# proiect2025_v18.net
KiCad netlist of a schematic drawn in EAGLE
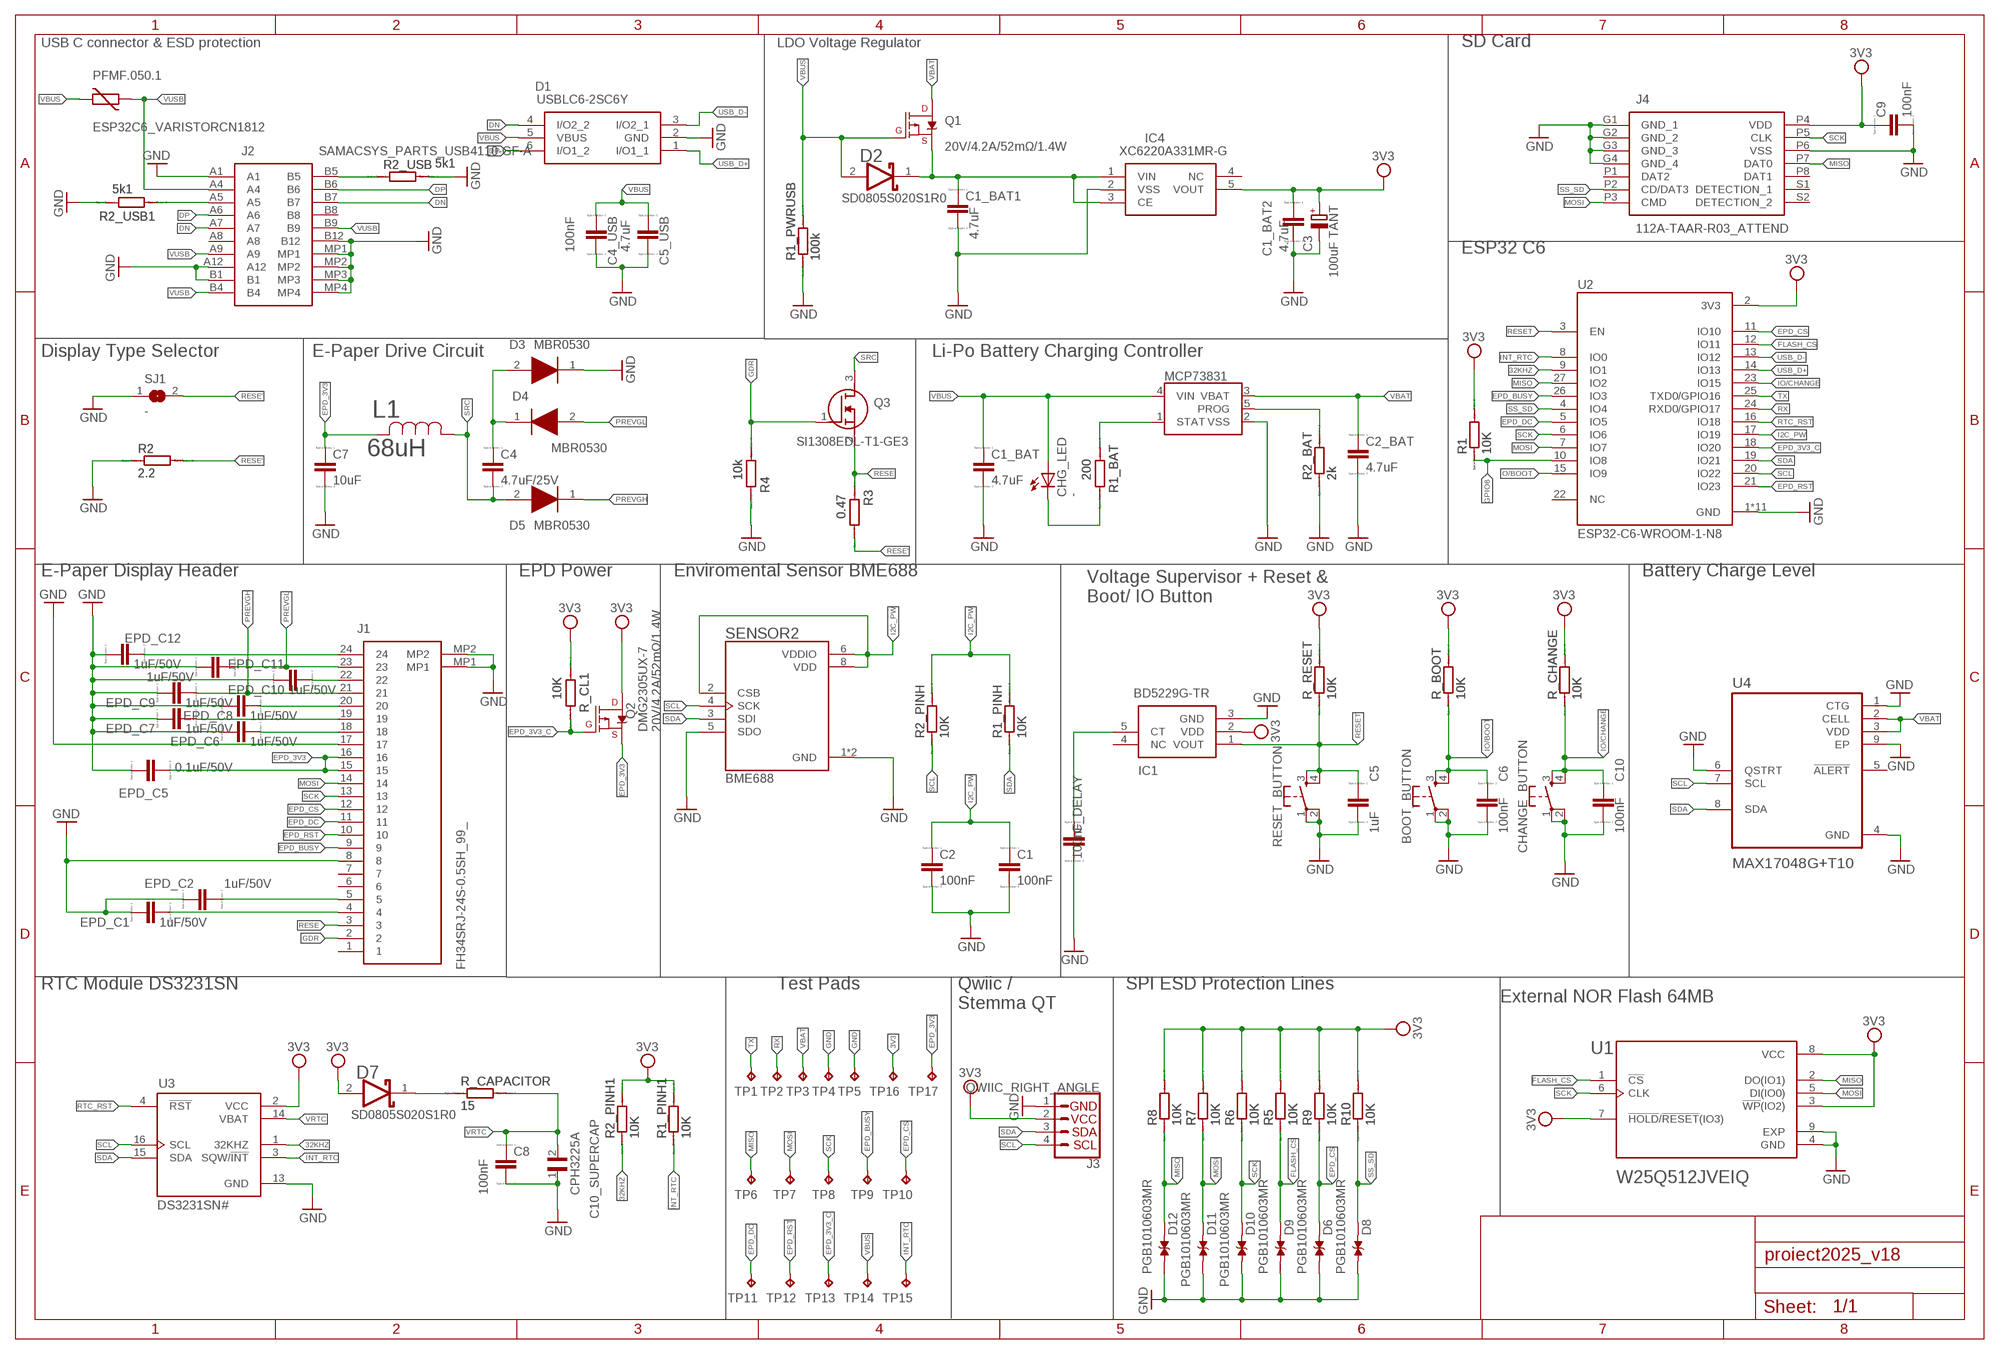
[diagram p0: schematic, sheet 1]

(export (version "E")
  (design (tool "Eeschema 10.0.6"))
  (components
    (comp (ref "BOOT_BUTTON")
      (value "BUTTON_CUSYOMV1")
      (footprint "eagle-import:MYBUTTON")
      (libsource (lib "eagle-import") (part "BUTTON_CUSYOMV1"))
    )
    (comp (ref "C1")
      (value "100nF")
      (footprint "eagle-import:EAGLE-LTSPICE_C0402")
      (libsource (lib "eagle-import") (part "EAGLE-LTSPICE_CC0402"))
    )
    (comp (ref "C1_BAT")
      (value "4.7uF")
      (footprint "eagle-import:EAGLE-LTSPICE_C0402")
      (libsource (lib "eagle-import") (part "EAGLE-LTSPICE_CC0402"))
    )
    (comp (ref "C1_BAT1")
      (value "4.7uF")
      (footprint "eagle-import:EAGLE-LTSPICE_C0402")
      (libsource (lib "eagle-import") (part "EAGLE-LTSPICE_CC0402"))
    )
    (comp (ref "C1_BAT2")
      (value "4.7uF")
      (footprint "eagle-import:EAGLE-LTSPICE_C0402")
      (libsource (lib "eagle-import") (part "EAGLE-LTSPICE_CC0402"))
    )
    (comp (ref "C2")
      (value "100nF")
      (footprint "eagle-import:EAGLE-LTSPICE_C0402")
      (libsource (lib "eagle-import") (part "EAGLE-LTSPICE_CC0402"))
    )
    (comp (ref "C2_BAT")
      (value "4.7uF")
      (footprint "eagle-import:EAGLE-LTSPICE_C0402")
      (libsource (lib "eagle-import") (part "EAGLE-LTSPICE_CC0402"))
    )
    (comp (ref "C3")
      (value "100uF TANT")
      (footprint "eagle-import:RCL_CT3528")
      (libsource (lib "eagle-import") (part "RCL_CPOL-EUCT3528"))
    )
    (comp (ref "C4")
      (value "4.7uF/25V")
      (footprint "eagle-import:EAGLE-LTSPICE_C0402")
      (libsource (lib "eagle-import") (part "EAGLE-LTSPICE_CC0402"))
    )
    (comp (ref "C4_USB")
      (value "100nF")
      (footprint "eagle-import:EAGLE-LTSPICE_C0402")
      (libsource (lib "eagle-import") (part "EAGLE-LTSPICE_CC0402"))
    )
    (comp (ref "C5")
      (value "1uF")
      (footprint "eagle-import:EAGLE-LTSPICE_C0402")
      (libsource (lib "eagle-import") (part "EAGLE-LTSPICE_CC0402"))
    )
    (comp (ref "C5_USB")
      (value "4.7uF")
      (footprint "eagle-import:EAGLE-LTSPICE_C0402")
      (libsource (lib "eagle-import") (part "EAGLE-LTSPICE_CC0402"))
    )
    (comp (ref "C6")
      (value "100nF")
      (footprint "eagle-import:EAGLE-LTSPICE_C0402")
      (libsource (lib "eagle-import") (part "EAGLE-LTSPICE_CC0402"))
    )
    (comp (ref "C7")
      (value "10uF")
      (footprint "eagle-import:EAGLE-LTSPICE_C0402")
      (libsource (lib "eagle-import") (part "EAGLE-LTSPICE_CC0402"))
    )
    (comp (ref "C8")
      (value "100nF")
      (footprint "eagle-import:EAGLE-LTSPICE_C0402")
      (libsource (lib "eagle-import") (part "EAGLE-LTSPICE_CC0402"))
    )
    (comp (ref "C9")
      (value "100nF")
      (footprint "eagle-import:EAGLE-LTSPICE_C0402")
      (libsource (lib "eagle-import") (part "EAGLE-LTSPICE_CC0402"))
    )
    (comp (ref "C10")
      (value "100nF")
      (footprint "eagle-import:EAGLE-LTSPICE_C0402")
      (libsource (lib "eagle-import") (part "EAGLE-LTSPICE_CC0402"))
    )
    (comp (ref "C10_SUPERCAP")
      (value "CPH3225A")
      (footprint "eagle-import:CAPCP3225X100N")
      (fields (field (name "MF") "Seiko Instruments"))
      (libsource (lib "eagle-import") (part "CPH3225A"))
    )
    (comp (ref "CHANGE_BUTTON")
      (value "BUTTON_CUSYOMV1")
      (footprint "eagle-import:MYBUTTON")
      (libsource (lib "eagle-import") (part "BUTTON_CUSYOMV1"))
    )
    (comp (ref "CHG_LED")
      (value "-")
      (footprint "eagle-import:ADAFRUIT_CHIP-LED0603")
      (libsource (lib "eagle-import") (part "ADAFRUIT_LEDCHIP-LED0603"))
    )
    (comp (ref "C_DELAY")
      (value "100nF")
      (footprint "eagle-import:EAGLE-LTSPICE_C0402")
      (libsource (lib "eagle-import") (part "EAGLE-LTSPICE_CC0402"))
    )
    (comp (ref "D1")
      (value "USBLC6-2SC6Y")
      (footprint "eagle-import:SOT95P280X145-6N")
      (fields (field (name "MF") "STMicroelectronics"))
      (libsource (lib "eagle-import") (part "USBLC6-2SC6Y"))
    )
    (comp (ref "D2")
      (value "ESP32_WROVER_AVX---SD0805S020S1R0_AVX_SD0805S020S1R0_0_0AVX_SD0805S020S1R0_0_0")
      (footprint "eagle-import:ESP32_WROVER_AVX---SD0805S020S1R0_AVX_SD0805S020S1R0_0")
      (fields
        (field (name "DIGIKEY_PART_NUMBER") "478-7800-1-ND")
        (field (name "MF") "AVX")
        (field (name "MOUSER_PART_NUMBER") "581-SD0805S020S1R0")
      )
      (libsource (lib "eagle-import") (part "ESP32_WROVER_AVX---SD0805S020S1R0_AVX_SD0805S020S1R0_0_0AVX_SD0805S020S1R0_0_0"))
    )
    (comp (ref "D3")
      (value "MBR0530")
      (footprint "eagle-import:SOD3716X135N")
      (fields (field (name "MF") "ON Semiconductor"))
      (libsource (lib "eagle-import") (part "MBR0530"))
    )
    (comp (ref "D4")
      (value "MBR0530")
      (footprint "eagle-import:SOD3716X135N")
      (fields (field (name "MF") "ON Semiconductor"))
      (libsource (lib "eagle-import") (part "MBR0530"))
    )
    (comp (ref "D5")
      (value "MBR0530")
      (footprint "eagle-import:SOD3716X135N")
      (fields (field (name "MF") "ON Semiconductor"))
      (libsource (lib "eagle-import") (part "MBR0530"))
    )
    (comp (ref "D6")
      (value "PGB1010603MR")
      (footprint "eagle-import:DIOC1608X36N")
      (fields (field (name "MF") "Littelfuse Inc."))
      (libsource (lib "eagle-import") (part "PGB1010603MR"))
    )
    (comp (ref "D7")
      (value "ESP32_WROVER_AVX---SD0805S020S1R0_AVX_SD0805S020S1R0_0_0AVX_SD0805S020S1R0_0_0")
      (footprint "eagle-import:ESP32_WROVER_AVX---SD0805S020S1R0_AVX_SD0805S020S1R0_0")
      (fields
        (field (name "DIGIKEY_PART_NUMBER") "478-7800-1-ND")
        (field (name "MF") "AVX")
        (field (name "MOUSER_PART_NUMBER") "581-SD0805S020S1R0")
      )
      (libsource (lib "eagle-import") (part "ESP32_WROVER_AVX---SD0805S020S1R0_AVX_SD0805S020S1R0_0_0AVX_SD0805S020S1R0_0_0"))
    )
    (comp (ref "D8")
      (value "PGB1010603MR")
      (footprint "eagle-import:DIOC1608X36N")
      (fields (field (name "MF") "Littelfuse Inc."))
      (libsource (lib "eagle-import") (part "PGB1010603MR"))
    )
    (comp (ref "D9")
      (value "PGB1010603MR")
      (footprint "eagle-import:DIOC1608X36N")
      (fields (field (name "MF") "Littelfuse Inc."))
      (libsource (lib "eagle-import") (part "PGB1010603MR"))
    )
    (comp (ref "D10")
      (value "PGB1010603MR")
      (footprint "eagle-import:DIOC1608X36N")
      (fields (field (name "MF") "Littelfuse Inc."))
      (libsource (lib "eagle-import") (part "PGB1010603MR"))
    )
    (comp (ref "D11")
      (value "PGB1010603MR")
      (footprint "eagle-import:DIOC1608X36N")
      (fields (field (name "MF") "Littelfuse Inc."))
      (libsource (lib "eagle-import") (part "PGB1010603MR"))
    )
    (comp (ref "D12")
      (value "PGB1010603MR")
      (footprint "eagle-import:DIOC1608X36N")
      (fields (field (name "MF") "Littelfuse Inc."))
      (libsource (lib "eagle-import") (part "PGB1010603MR"))
    )
    (comp (ref "EPD_C1")
      (value "1uF/50V")
      (footprint "eagle-import:EAGLE-LTSPICE_C0402")
      (libsource (lib "eagle-import") (part "EAGLE-LTSPICE_CC0402"))
    )
    (comp (ref "EPD_C2")
      (value "1uF/50V")
      (footprint "eagle-import:EAGLE-LTSPICE_C0402")
      (libsource (lib "eagle-import") (part "EAGLE-LTSPICE_CC0402"))
    )
    (comp (ref "EPD_C5")
      (value "0.1uF/50V")
      (footprint "eagle-import:EAGLE-LTSPICE_C0402")
      (libsource (lib "eagle-import") (part "EAGLE-LTSPICE_CC0402"))
    )
    (comp (ref "EPD_C6")
      (value "1uF/50V")
      (footprint "eagle-import:EAGLE-LTSPICE_C0402")
      (libsource (lib "eagle-import") (part "EAGLE-LTSPICE_CC0402"))
    )
    (comp (ref "EPD_C7")
      (value "1uF/50V")
      (footprint "eagle-import:EAGLE-LTSPICE_C0402")
      (libsource (lib "eagle-import") (part "EAGLE-LTSPICE_CC0402"))
    )
    (comp (ref "EPD_C8")
      (value "1uF/50V")
      (footprint "eagle-import:EAGLE-LTSPICE_C0402")
      (libsource (lib "eagle-import") (part "EAGLE-LTSPICE_CC0402"))
    )
    (comp (ref "EPD_C9")
      (value "1uF/50V")
      (footprint "eagle-import:EAGLE-LTSPICE_C0402")
      (libsource (lib "eagle-import") (part "EAGLE-LTSPICE_CC0402"))
    )
    (comp (ref "EPD_C10")
      (value "1uF/50V")
      (footprint "eagle-import:EAGLE-LTSPICE_C0402")
      (libsource (lib "eagle-import") (part "EAGLE-LTSPICE_CC0402"))
    )
    (comp (ref "EPD_C11")
      (value "1uF/50V")
      (footprint "eagle-import:EAGLE-LTSPICE_C0402")
      (libsource (lib "eagle-import") (part "EAGLE-LTSPICE_CC0402"))
    )
    (comp (ref "EPD_C12")
      (value "1uF/50V")
      (footprint "eagle-import:EAGLE-LTSPICE_C0402")
      (libsource (lib "eagle-import") (part "EAGLE-LTSPICE_CC0402"))
    )
    (comp (ref "IC1")
      (value "BD5229G-TR")
      (footprint "eagle-import:SOT95P280X125-5N")
      (fields (field (name "MOUSER_PART_NUMBER") "755-BD5229G-TR"))
      (libsource (lib "eagle-import") (part "BD5229G-TR"))
    )
    (comp (ref "IC4")
      (value "XC6220A331MR-G")
      (footprint "eagle-import:SOT95P280X120-5N")
      (fields (field (name "MOUSER_PART_NUMBER") "865-XC6220A331MR-G"))
      (libsource (lib "eagle-import") (part "XC6220A331MR-G"))
    )
    (comp (ref "J1")
      (value "FH34SRJ-24S-0.5SH_99_")
      (footprint "eagle-import:FH34SRJ24S05SH99")
      (fields
        (field (name "MANUFACTURER_PART_NUMBER") "FH34SRJ-24S-0.5SH(99)")
        (field (name "MOUSER_PART_NUMBER") "798-FH34SRJ24S05SH99")
      )
      (libsource (lib "eagle-import") (part "FH34SRJ-24S-0.5SH_99_"))
    )
    (comp (ref "J2")
      (value "SAMACSYS_PARTS_USB4110-GF-A")
      (footprint "eagle-import:SAMACSYS_PARTS_USB4110GFA")
      (fields
        (field (name "MANUFACTURER_PART_NUMBER") "USB4110-GF-A")
        (field (name "MOUSER_PART_NUMBER") "640-USB4110-GF-A")
      )
      (libsource (lib "eagle-import") (part "SAMACSYS_PARTS_USB4110-GF-A"))
    )
    (comp (ref "J3")
      (value "QWIIC_RIGHT_ANGLE")
      (footprint "eagle-import:JST04_1MM_RA")
      (libsource (lib "eagle-import") (part "QWIIC_CONNECTORJS-1MM"))
    )
    (comp (ref "J4")
      (value "112A-TAAR-R03_ATTEND")
      (footprint "eagle-import:112ATAARR03ATTEND")
      (fields (field (name "MANUFACTURER_PART_NUMBER") "112A-TAAR-R03 ATTEND"))
      (libsource (lib "eagle-import") (part "112A-TAAR-R03_ATTEND"))
    )
    (comp (ref "L1")
      (value "68uH")
      (footprint "eagle-import:IND_4828-WE-TPC_WRE")
      (fields
        (field (name "MANUFACTURER_PART_NUMBER") "744043680")
        (field (name "COPYRIGHT") "Copyright (C) 2024 Ultra Librarian. All rights reserved.")
      )
      (libsource (lib "eagle-import") (part "744043680IND_4828-WE-TPC_WRE"))
    )
    (comp (ref "MCP73831")
      (value "ESP32_WROVER_SPARKFUN-IC-POWER_MCP73831")
      (footprint "eagle-import:ESP32_WROVER_SPARKFUN-IC-POWER_SOT23-5")
      (libsource (lib "eagle-import") (part "ESP32_WROVER_SPARKFUN-IC-POWER_MCP73831"))
    )
    (comp (ref "PFMF.050.1")
      (value "ESP32C6_VARISTORCN1812")
      (footprint "eagle-import:ESP32C6_VARISTOR_CT_CN1812")
      (libsource (lib "eagle-import") (part "ESP32C6_VARISTORCN1812"))
    )
    (comp (ref "Q1")
      (value "20V/4.2A/52mΩ/1.4W")
      (footprint "eagle-import:ESP32_WROVER_SPARKFUN-DISCRETESEMI_SOT23-3")
      (libsource (lib "eagle-import") (part "ESP32_WROVER_SPARKFUN-DISCRETESEMI_MOSFET_PCH-DMG2305UX-7"))
    )
    (comp (ref "Q2")
      (value "20V/4.2A/52mΩ/1.4W")
      (footprint "eagle-import:ESP32_WROVER_SPARKFUN-DISCRETESEMI_SOT23-3")
      (libsource (lib "eagle-import") (part "ESP32_WROVER_SPARKFUN-DISCRETESEMI_MOSFET_PCH-DMG2305UX-7"))
    )
    (comp (ref "Q3")
      (value "SI1308EDL-T1-GE3")
      (footprint "eagle-import:SOT65P210X110-3N")
      (fields (field (name "MF") "Vishay Siliconix"))
      (libsource (lib "eagle-import") (part "SI1308EDL-T1-GE3"))
    )
    (comp (ref "R1")
      (value "10K")
      (footprint "eagle-import:ESP32_WROVER_EAGLE-LTSPICE_R0402")
      (libsource (lib "eagle-import") (part "ESP32_WROVER_EAGLE-LTSPICE_RR0402"))
    )
    (comp (ref "R1_BAT")
      (value "200")
      (footprint "eagle-import:ESP32_WROVER_EAGLE-LTSPICE_R0402")
      (libsource (lib "eagle-import") (part "ESP32_WROVER_EAGLE-LTSPICE_RR0402"))
    )
    (comp (ref "R1_PINH")
      (value "10K")
      (footprint "eagle-import:ESP32_WROVER_EAGLE-LTSPICE_R0402")
      (libsource (lib "eagle-import") (part "ESP32_WROVER_EAGLE-LTSPICE_RR0402"))
    )
    (comp (ref "R1_PINH1")
      (value "10K")
      (footprint "eagle-import:ESP32_WROVER_EAGLE-LTSPICE_R0402")
      (libsource (lib "eagle-import") (part "ESP32_WROVER_EAGLE-LTSPICE_RR0402"))
    )
    (comp (ref "R1_PWRUSB")
      (value "100k")
      (footprint "eagle-import:ESP32_WROVER_EAGLE-LTSPICE_R0402")
      (libsource (lib "eagle-import") (part "ESP32_WROVER_EAGLE-LTSPICE_RR0402"))
    )
    (comp (ref "R2")
      (value "2.2")
      (footprint "eagle-import:ESP32_WROVER_EAGLE-LTSPICE_R0402")
      (libsource (lib "eagle-import") (part "ESP32_WROVER_EAGLE-LTSPICE_RR0402"))
    )
    (comp (ref "R2_BAT")
      (value "2k")
      (footprint "eagle-import:ESP32_WROVER_EAGLE-LTSPICE_R0402")
      (libsource (lib "eagle-import") (part "ESP32_WROVER_EAGLE-LTSPICE_RR0402"))
    )
    (comp (ref "R2_PINH")
      (value "10K")
      (footprint "eagle-import:ESP32_WROVER_EAGLE-LTSPICE_R0402")
      (libsource (lib "eagle-import") (part "ESP32_WROVER_EAGLE-LTSPICE_RR0402"))
    )
    (comp (ref "R2_PINH1")
      (value "10K")
      (footprint "eagle-import:ESP32_WROVER_EAGLE-LTSPICE_R0402")
      (libsource (lib "eagle-import") (part "ESP32_WROVER_EAGLE-LTSPICE_RR0402"))
    )
    (comp (ref "R2_USB")
      (value "5k1")
      (footprint "eagle-import:ESP32_WROVER_EAGLE-LTSPICE_R0402")
      (libsource (lib "eagle-import") (part "ESP32_WROVER_EAGLE-LTSPICE_RR0402"))
    )
    (comp (ref "R2_USB1")
      (value "5k1")
      (footprint "eagle-import:ESP32_WROVER_EAGLE-LTSPICE_R0402")
      (libsource (lib "eagle-import") (part "ESP32_WROVER_EAGLE-LTSPICE_RR0402"))
    )
    (comp (ref "R3")
      (value "0.47")
      (footprint "eagle-import:ESP32_WROVER_EAGLE-LTSPICE_R0402")
      (libsource (lib "eagle-import") (part "ESP32_WROVER_EAGLE-LTSPICE_RR0402"))
    )
    (comp (ref "R4")
      (value "10k")
      (footprint "eagle-import:ESP32_WROVER_EAGLE-LTSPICE_R0402")
      (libsource (lib "eagle-import") (part "ESP32_WROVER_EAGLE-LTSPICE_RR0402"))
    )
    (comp (ref "R5")
      (value "10K")
      (footprint "eagle-import:ESP32_WROVER_EAGLE-LTSPICE_R0402")
      (libsource (lib "eagle-import") (part "ESP32_WROVER_EAGLE-LTSPICE_RR0402"))
    )
    (comp (ref "R6")
      (value "10K")
      (footprint "eagle-import:ESP32_WROVER_EAGLE-LTSPICE_R0402")
      (libsource (lib "eagle-import") (part "ESP32_WROVER_EAGLE-LTSPICE_RR0402"))
    )
    (comp (ref "R7")
      (value "10K")
      (footprint "eagle-import:ESP32_WROVER_EAGLE-LTSPICE_R0402")
      (libsource (lib "eagle-import") (part "ESP32_WROVER_EAGLE-LTSPICE_RR0402"))
    )
    (comp (ref "R8")
      (value "10K")
      (footprint "eagle-import:ESP32_WROVER_EAGLE-LTSPICE_R0402")
      (libsource (lib "eagle-import") (part "ESP32_WROVER_EAGLE-LTSPICE_RR0402"))
    )
    (comp (ref "R9")
      (value "10K")
      (footprint "eagle-import:ESP32_WROVER_EAGLE-LTSPICE_R0402")
      (libsource (lib "eagle-import") (part "ESP32_WROVER_EAGLE-LTSPICE_RR0402"))
    )
    (comp (ref "R10")
      (value "10K")
      (footprint "eagle-import:ESP32_WROVER_EAGLE-LTSPICE_R0402")
      (libsource (lib "eagle-import") (part "ESP32_WROVER_EAGLE-LTSPICE_RR0402"))
    )
    (comp (ref "RESET_BUTTON")
      (value "BUTTON_CUSYOMV1")
      (footprint "eagle-import:MYBUTTON")
      (libsource (lib "eagle-import") (part "BUTTON_CUSYOMV1"))
    )
    (comp (ref "R_BOOT")
      (value "10K")
      (footprint "eagle-import:ESP32_WROVER_EAGLE-LTSPICE_R0402")
      (libsource (lib "eagle-import") (part "ESP32_WROVER_EAGLE-LTSPICE_RR0402"))
    )
    (comp (ref "R_CAPACITOR")
      (value "15")
      (footprint "eagle-import:ESP32_WROVER_EAGLE-LTSPICE_R0402")
      (libsource (lib "eagle-import") (part "ESP32_WROVER_EAGLE-LTSPICE_RR0402"))
    )
    (comp (ref "R_CHANGE")
      (value "10K")
      (footprint "eagle-import:ESP32_WROVER_EAGLE-LTSPICE_R0402")
      (libsource (lib "eagle-import") (part "ESP32_WROVER_EAGLE-LTSPICE_RR0402"))
    )
    (comp (ref "R_CL1")
      (value "10K")
      (footprint "eagle-import:ESP32_WROVER_EAGLE-LTSPICE_R0402")
      (libsource (lib "eagle-import") (part "ESP32_WROVER_EAGLE-LTSPICE_RR0402"))
    )
    (comp (ref "R_RESET")
      (value "10K")
      (footprint "eagle-import:ESP32_WROVER_EAGLE-LTSPICE_R0402")
      (libsource (lib "eagle-import") (part "ESP32_WROVER_EAGLE-LTSPICE_RR0402"))
    )
    (comp (ref "SENSOR2")
      (value "ESP32_WROVER_BME680_BME680")
      (footprint "eagle-import:ESP32_WROVER_BME680_PSON80P300X300X100-8N")
      (fields (field (name "MF") "Bosch Sensortec") (field (name "MP") "BME680"))
      (libsource (lib "eagle-import") (part "ESP32_WROVER_BME680_BME680"))
    )
    (comp (ref "SJ1") (value "-") (footprint "eagle-import:SJ") (libsource (lib "eagle-import") (part "SJ")))
    (comp (ref "TP1")
      (value "TPTP20R")
      (footprint "eagle-import:TP20R")
      (libsource (lib "eagle-import") (part "TPTP20R"))
    )
    (comp (ref "TP2")
      (value "TPTP20R")
      (footprint "eagle-import:TP20R")
      (libsource (lib "eagle-import") (part "TPTP20R"))
    )
    (comp (ref "TP3")
      (value "TPTP20R")
      (footprint "eagle-import:TP20R")
      (libsource (lib "eagle-import") (part "TPTP20R"))
    )
    (comp (ref "TP4")
      (value "TPTP20R")
      (footprint "eagle-import:TP20R")
      (libsource (lib "eagle-import") (part "TPTP20R"))
    )
    (comp (ref "TP5")
      (value "TPTP20R")
      (footprint "eagle-import:TP20R")
      (libsource (lib "eagle-import") (part "TPTP20R"))
    )
    (comp (ref "TP6")
      (value "TPTP20R")
      (footprint "eagle-import:TP20R")
      (libsource (lib "eagle-import") (part "TPTP20R"))
    )
    (comp (ref "TP7")
      (value "TPTP20R")
      (footprint "eagle-import:TP20R")
      (libsource (lib "eagle-import") (part "TPTP20R"))
    )
    (comp (ref "TP8")
      (value "TPTP20R")
      (footprint "eagle-import:TP20R")
      (libsource (lib "eagle-import") (part "TPTP20R"))
    )
    (comp (ref "TP9")
      (value "TPTP20R")
      (footprint "eagle-import:TP20R")
      (libsource (lib "eagle-import") (part "TPTP20R"))
    )
    (comp (ref "TP10")
      (value "TPTP20R")
      (footprint "eagle-import:TP20R")
      (libsource (lib "eagle-import") (part "TPTP20R"))
    )
    (comp (ref "TP11")
      (value "TPTP20R")
      (footprint "eagle-import:TP20R")
      (libsource (lib "eagle-import") (part "TPTP20R"))
    )
    (comp (ref "TP12")
      (value "TPTP20R")
      (footprint "eagle-import:TP20R")
      (libsource (lib "eagle-import") (part "TPTP20R"))
    )
    (comp (ref "TP13")
      (value "TPTP20R")
      (footprint "eagle-import:TP20R")
      (libsource (lib "eagle-import") (part "TPTP20R"))
    )
    (comp (ref "TP14")
      (value "TPTP20R")
      (footprint "eagle-import:TP20R")
      (libsource (lib "eagle-import") (part "TPTP20R"))
    )
    (comp (ref "TP15")
      (value "TPTP20R")
      (footprint "eagle-import:TP20R")
      (libsource (lib "eagle-import") (part "TPTP20R"))
    )
    (comp (ref "TP16")
      (value "TPTP20R")
      (footprint "eagle-import:TP20R")
      (libsource (lib "eagle-import") (part "TPTP20R"))
    )
    (comp (ref "TP17")
      (value "TPTP20R")
      (footprint "eagle-import:TP20R")
      (libsource (lib "eagle-import") (part "TPTP20R"))
    )
    (comp (ref "U1")
      (value "W25Q512JVEIQ")
      (footprint "eagle-import:SON127P600X800X80-9N")
      (fields (field (name "MF") "Winbond Electronics"))
      (libsource (lib "eagle-import") (part "W25Q512JVEIQ"))
    )
    (comp (ref "U2")
      (value "ESP32-C6-WROOM-1-N8")
      (footprint "eagle-import:XCVR_ESP32-C6-WROOM-1-N8")
      (fields (field (name "MF") "Espressif Systems"))
      (libsource (lib "eagle-import") (part "ESP32-C6-WROOM-1-N8"))
    )
    (comp (ref "U3")
      (value "DS3231SN#")
      (footprint "eagle-import:SOIC127P1032X265-16N")
      (fields (field (name "MF") "Analog Devices"))
      (libsource (lib "eagle-import") (part "DS3231SN#"))
    )
    (comp (ref "U4")
      (value "MAX17048G+T10")
      (footprint "eagle-import:SON50P200X200X80-9N")
      (fields (field (name "MF") "Analog Devices"))
      (libsource (lib "eagle-import") (part "MAX17048G+T10"))
    )
  )
  (nets
    (net (code "1") (name "3V3") (class "Default")
      (node (ref "C1_BAT2") (pin "1") (pinfunction "1_1") (pintype "passive"))
      (node (ref "C3") (pin "+") (pinfunction "+_+") (pintype "passive"))
      (node (ref "C9") (pin "1") (pinfunction "1_1") (pintype "passive"))
      (node (ref "D7") (pin "2") (pinfunction "ANODE_2") (pintype "bidirectional"))
      (node (ref "IC1") (pin "2") (pinfunction "VDD_2") (pintype "bidirectional"))
      (node (ref "IC4") (pin "5") (pinfunction "VOUT_5") (pintype "bidirectional"))
      (node (ref "J3") (pin "2") (pinfunction "2_2") (pintype "power_in"))
      (node (ref "J4") (pin "P4") (pinfunction "VDD_P4") (pintype "bidirectional"))
      (node (ref "Q2") (pin "3") (pinfunction "D_3") (pintype "bidirectional"))
      (node (ref "R1") (pin "2") (pinfunction "2_2") (pintype "passive"))
      (node (ref "R10") (pin "2") (pinfunction "2_2") (pintype "passive"))
      (node (ref "R1_PINH1") (pin "2") (pinfunction "2_2") (pintype "passive"))
      (node (ref "R2_PINH1") (pin "2") (pinfunction "2_2") (pintype "passive"))
      (node (ref "R5") (pin "2") (pinfunction "2_2") (pintype "passive"))
      (node (ref "R6") (pin "2") (pinfunction "2_2") (pintype "passive"))
      (node (ref "R7") (pin "2") (pinfunction "2_2") (pintype "passive"))
      (node (ref "R8") (pin "2") (pinfunction "2_2") (pintype "passive"))
      (node (ref "R9") (pin "2") (pinfunction "2_2") (pintype "passive"))
      (node (ref "R_BOOT") (pin "2") (pinfunction "2_2") (pintype "passive"))
      (node (ref "R_CHANGE") (pin "2") (pinfunction "2_2") (pintype "passive"))
      (node (ref "R_CL1") (pin "2") (pinfunction "2_2") (pintype "passive"))
      (node (ref "R_RESET") (pin "2") (pinfunction "2_2") (pintype "passive"))
      (node (ref "TP16") (pin "TP") (pinfunction "TP_TP") (pintype "input"))
      (node (ref "U1") (pin "3") (pinfunction "~{WP}(IO2)_3") (pintype "bidirectional"))
      (node (ref "U1") (pin "7") (pinfunction "~{HOLD}/~{RESET}(IO3)_7") (pintype "bidirectional"))
      (node (ref "U1") (pin "8") (pinfunction "VCC_8") (pintype "power_in"))
      (node (ref "U2") (pin "2") (pinfunction "3V3_2") (pintype "power_in"))
      (node (ref "U3") (pin "2") (pinfunction "VCC_2") (pintype "power_in"))
    )
    (net (code "2") (name "32KHZ") (class "Default")
      (node (ref "R2_PINH1") (pin "1") (pinfunction "1_1") (pintype "passive"))
      (node (ref "U2") (pin "9") (pinfunction "IO1_9") (pintype "bidirectional"))
      (node (ref "U3") (pin "1") (pinfunction "32KHZ_1") (pintype "output"))
    )
    (net (code "3") (name "DN") (class "Default")
      (node (ref "D1") (pin "4") (pinfunction "I/O2_2_4") (pintype "bidirectional"))
      (node (ref "J2") (pin "A7") (pinfunction "A7_A7") (pintype "bidirectional"))
      (node (ref "J2") (pin "B7") (pinfunction "B7_B7") (pintype "bidirectional"))
    )
    (net (code "4") (name "DP") (class "Default")
      (node (ref "D1") (pin "6") (pinfunction "I/O1_2_6") (pintype "bidirectional"))
      (node (ref "J2") (pin "A6") (pinfunction "A6_A6") (pintype "bidirectional"))
      (node (ref "J2") (pin "B6") (pinfunction "B6_B6") (pintype "bidirectional"))
    )
    (net (code "5") (name "EPD_3V3") (class "Default")
      (node (ref "C7") (pin "1") (pinfunction "1_1") (pintype "passive"))
      (node (ref "EPD_C5") (pin "2") (pinfunction "2_2") (pintype "passive"))
      (node (ref "J1") (pin "15") (pinfunction "15_15") (pintype "bidirectional"))
      (node (ref "J1") (pin "16") (pinfunction "16_16") (pintype "bidirectional"))
      (node (ref "L1") (pin "2") (pinfunction "2_2") (pintype "passive"))
      (node (ref "Q2") (pin "2") (pinfunction "S_2") (pintype "bidirectional"))
      (node (ref "TP17") (pin "TP") (pinfunction "TP_TP") (pintype "input"))
    )
    (net (code "6") (name "EPD_3V3_C") (class "Default")
      (node (ref "Q2") (pin "1") (pinfunction "G_1") (pintype "bidirectional"))
      (node (ref "R_CL1") (pin "1") (pinfunction "1_1") (pintype "passive"))
      (node (ref "TP13") (pin "TP") (pinfunction "TP_TP") (pintype "input"))
      (node (ref "U2") (pin "18") (pinfunction "IO20_18") (pintype "bidirectional"))
    )
    (net (code "7") (name "EPD_BUSY") (class "Default")
      (node (ref "J1") (pin "9") (pinfunction "9_9") (pintype "bidirectional"))
      (node (ref "TP9") (pin "TP") (pinfunction "TP_TP") (pintype "input"))
      (node (ref "U2") (pin "26") (pinfunction "IO3_26") (pintype "bidirectional"))
    )
    (net (code "8") (name "EPD_CS") (class "Default")
      (node (ref "D6") (pin "2") (pinfunction "2_2") (pintype "passive"))
      (node (ref "J1") (pin "12") (pinfunction "12_12") (pintype "bidirectional"))
      (node (ref "R9") (pin "1") (pinfunction "1_1") (pintype "passive"))
      (node (ref "TP10") (pin "TP") (pinfunction "TP_TP") (pintype "input"))
      (node (ref "U2") (pin "11") (pinfunction "IO10_11") (pintype "bidirectional"))
    )
    (net (code "9") (name "EPD_DC") (class "Default")
      (node (ref "J1") (pin "11") (pinfunction "11_11") (pintype "bidirectional"))
      (node (ref "TP11") (pin "TP") (pinfunction "TP_TP") (pintype "input"))
      (node (ref "U2") (pin "5") (pinfunction "IO5_5") (pintype "bidirectional"))
    )
    (net (code "10") (name "EPD_RST") (class "Default")
      (node (ref "J1") (pin "10") (pinfunction "10_10") (pintype "bidirectional"))
      (node (ref "TP12") (pin "TP") (pinfunction "TP_TP") (pintype "input"))
      (node (ref "U2") (pin "21") (pinfunction "IO23_21") (pintype "bidirectional"))
    )
    (net (code "11") (name "FLASH_CS") (class "Default")
      (node (ref "D9") (pin "2") (pinfunction "2_2") (pintype "passive"))
      (node (ref "R5") (pin "1") (pinfunction "1_1") (pintype "passive"))
      (node (ref "U1") (pin "1") (pinfunction "~{CS}_1") (pintype "input"))
      (node (ref "U2") (pin "12") (pinfunction "IO11_12") (pintype "bidirectional"))
    )
    (net (code "12") (name "GDR") (class "Default")
      (node (ref "J1") (pin "2") (pinfunction "2_2") (pintype "bidirectional"))
      (node (ref "Q3") (pin "1") (pinfunction "G_1") (pintype "bidirectional"))
      (node (ref "R4") (pin "2") (pinfunction "2_2") (pintype "passive"))
    )
    (net (code "13") (name "GND") (class "Default")
      (node (ref "BOOT_BUTTON") (pin "1") (pinfunction "1_1") (pintype "passive"))
      (node (ref "BOOT_BUTTON") (pin "2") (pinfunction "2_2") (pintype "passive"))
      (node (ref "C1") (pin "2") (pinfunction "2_2") (pintype "passive"))
      (node (ref "C10") (pin "2") (pinfunction "2_2") (pintype "passive"))
      (node (ref "C10_SUPERCAP") (pin "1") (pinfunction "1_1") (pintype "passive"))
      (node (ref "C1_BAT") (pin "2") (pinfunction "2_2") (pintype "passive"))
      (node (ref "C1_BAT1") (pin "2") (pinfunction "2_2") (pintype "passive"))
      (node (ref "C1_BAT2") (pin "2") (pinfunction "2_2") (pintype "passive"))
      (node (ref "C2") (pin "2") (pinfunction "2_2") (pintype "passive"))
      (node (ref "C2_BAT") (pin "2") (pinfunction "2_2") (pintype "passive"))
      (node (ref "C3") (pin "-") (pinfunction "-_-") (pintype "passive"))
      (node (ref "C4_USB") (pin "2") (pinfunction "2_2") (pintype "passive"))
      (node (ref "C5") (pin "2") (pinfunction "2_2") (pintype "passive"))
      (node (ref "C5_USB") (pin "2") (pinfunction "2_2") (pintype "passive"))
      (node (ref "C6") (pin "2") (pinfunction "2_2") (pintype "passive"))
      (node (ref "C7") (pin "2") (pinfunction "2_2") (pintype "passive"))
      (node (ref "C8") (pin "2") (pinfunction "2_2") (pintype "passive"))
      (node (ref "C9") (pin "2") (pinfunction "2_2") (pintype "passive"))
      (node (ref "CHANGE_BUTTON") (pin "1") (pinfunction "1_1") (pintype "passive"))
      (node (ref "CHANGE_BUTTON") (pin "2") (pinfunction "2_2") (pintype "passive"))
      (node (ref "C_DELAY") (pin "2") (pinfunction "2_2") (pintype "passive"))
      (node (ref "D1") (pin "2") (pinfunction "GND_2") (pintype "bidirectional"))
      (node (ref "D10") (pin "1") (pinfunction "1_1") (pintype "passive"))
      (node (ref "D11") (pin "1") (pinfunction "1_1") (pintype "passive"))
      (node (ref "D12") (pin "1") (pinfunction "1_1") (pintype "passive"))
      (node (ref "D3") (pin "1") (pinfunction "K_1") (pintype "bidirectional"))
      (node (ref "D6") (pin "1") (pinfunction "1_1") (pintype "passive"))
      (node (ref "D8") (pin "1") (pinfunction "1_1") (pintype "passive"))
      (node (ref "D9") (pin "1") (pinfunction "1_1") (pintype "passive"))
      (node (ref "EPD_C1") (pin "1") (pinfunction "1_1") (pintype "passive"))
      (node (ref "EPD_C10") (pin "1") (pinfunction "1_1") (pintype "passive"))
      (node (ref "EPD_C11") (pin "1") (pinfunction "1_1") (pintype "passive"))
      (node (ref "EPD_C12") (pin "1") (pinfunction "1_1") (pintype "passive"))
      (node (ref "EPD_C2") (pin "1") (pinfunction "1_1") (pintype "passive"))
      (node (ref "EPD_C5") (pin "1") (pinfunction "1_1") (pintype "passive"))
      (node (ref "EPD_C6") (pin "1") (pinfunction "1_1") (pintype "passive"))
      (node (ref "EPD_C7") (pin "1") (pinfunction "1_1") (pintype "passive"))
      (node (ref "EPD_C8") (pin "1") (pinfunction "1_1") (pintype "passive"))
      (node (ref "EPD_C9") (pin "1") (pinfunction "1_1") (pintype "passive"))
      (node (ref "IC1") (pin "3") (pinfunction "GND_3") (pintype "bidirectional"))
      (node (ref "IC4") (pin "2") (pinfunction "VSS_2") (pintype "bidirectional"))
      (node (ref "J1") (pin "17") (pinfunction "17_17") (pintype "bidirectional"))
      (node (ref "J1") (pin "8") (pinfunction "8_8") (pintype "bidirectional"))
      (node (ref "J1") (pin "MP1") (pinfunction "MP1_MP1") (pintype "bidirectional"))
      (node (ref "J1") (pin "MP2") (pinfunction "MP2_MP2") (pintype "bidirectional"))
      (node (ref "J2") (pin "A1") (pinfunction "A1_A1") (pintype "bidirectional"))
      (node (ref "J2") (pin "A12") (pinfunction "A12_A12") (pintype "bidirectional"))
      (node (ref "J2") (pin "B1") (pinfunction "B1_B1") (pintype "bidirectional"))
      (node (ref "J2") (pin "B12") (pinfunction "B12_B12") (pintype "bidirectional"))
      (node (ref "J2") (pin "MP1") (pinfunction "MP1_MP1") (pintype "bidirectional"))
      (node (ref "J2") (pin "MP2") (pinfunction "MP2_MP2") (pintype "bidirectional"))
      (node (ref "J2") (pin "MP3") (pinfunction "MP3_MP3") (pintype "bidirectional"))
      (node (ref "J2") (pin "MP4") (pinfunction "MP4_MP4") (pintype "bidirectional"))
      (node (ref "J3") (pin "1") (pinfunction "1_1") (pintype "power_in"))
      (node (ref "J4") (pin "G1") (pinfunction "GND_1_G1") (pintype "bidirectional"))
      (node (ref "J4") (pin "G2") (pinfunction "GND_2_G2") (pintype "bidirectional"))
      (node (ref "J4") (pin "G3") (pinfunction "GND_3_G3") (pintype "bidirectional"))
      (node (ref "J4") (pin "G4") (pinfunction "GND_4_G4") (pintype "bidirectional"))
      (node (ref "J4") (pin "P6") (pinfunction "VSS_P6") (pintype "bidirectional"))
      (node (ref "MCP73831") (pin "2") (pinfunction "VSS_2") (pintype "power_in"))
      (node (ref "R1_PWRUSB") (pin "1") (pinfunction "1_1") (pintype "passive"))
      (node (ref "R2") (pin "1") (pinfunction "1_1") (pintype "passive"))
      (node (ref "R2_BAT") (pin "1") (pinfunction "1_1") (pintype "passive"))
      (node (ref "R2_USB") (pin "2") (pinfunction "2_2") (pintype "passive"))
      (node (ref "R2_USB1") (pin "1") (pinfunction "1_1") (pintype "passive"))
      (node (ref "R4") (pin "1") (pinfunction "1_1") (pintype "passive"))
      (node (ref "RESET_BUTTON") (pin "1") (pinfunction "1_1") (pintype "passive"))
      (node (ref "RESET_BUTTON") (pin "2") (pinfunction "2_2") (pintype "passive"))
      (node (ref "SENSOR2") (pin "1") (pinfunction "GND_1") (pintype "power_in"))
      (node (ref "SENSOR2") (pin "5") (pinfunction "SDO_5") (pintype "bidirectional"))
      (node (ref "SENSOR2") (pin "7") (pinfunction "GND_7") (pintype "power_in"))
      (node (ref "SJ1") (pin "1") (pinfunction "1_1") (pintype "passive"))
      (node (ref "TP4") (pin "TP") (pinfunction "TP_TP") (pintype "input"))
      (node (ref "TP5") (pin "TP") (pinfunction "TP_TP") (pintype "input"))
      (node (ref "U1") (pin "4") (pinfunction "GND_4") (pintype "power_in"))
      (node (ref "U1") (pin "9") (pinfunction "EXP_9") (pintype "passive"))
      (node (ref "U2") (pin "1") (pinfunction "GND_1") (pintype "power_in"))
      (node (ref "U2") (pin "28") (pinfunction "GND_28") (pintype "power_in"))
      (node (ref "U2") (pin "29_1") (pinfunction "GND_29_1") (pintype "power_in"))
      (node (ref "U2") (pin "29_2") (pinfunction "GND_29_2") (pintype "power_in"))
      (node (ref "U2") (pin "29_3") (pinfunction "GND_29_3") (pintype "power_in"))
      (node (ref "U2") (pin "29_4") (pinfunction "GND_29_4") (pintype "power_in"))
      (node (ref "U2") (pin "29_5") (pinfunction "GND_29_5") (pintype "power_in"))
      (node (ref "U2") (pin "29_6") (pinfunction "GND_29_6") (pintype "power_in"))
      (node (ref "U2") (pin "29_7") (pinfunction "GND_29_7") (pintype "power_in"))
      (node (ref "U2") (pin "29_8") (pinfunction "GND_29_8") (pintype "power_in"))
      (node (ref "U2") (pin "29_9") (pinfunction "GND_29_9") (pintype "power_in"))
      (node (ref "U3") (pin "13") (pinfunction "GND_13") (pintype "power_in"))
      (node (ref "U4") (pin "1") (pinfunction "CTG_1") (pintype "power_in"))
      (node (ref "U4") (pin "4") (pinfunction "GND_4") (pintype "power_in"))
      (node (ref "U4") (pin "6") (pinfunction "QSTRT_6") (pintype "input"))
      (node (ref "U4") (pin "9") (pinfunction "EP_9") (pintype "power_in"))
    )
    (net (code "14") (name "GPIO8") (class "Default")
      (node (ref "R1") (pin "1") (pinfunction "1_1") (pintype "passive"))
      (node (ref "U2") (pin "10") (pinfunction "IO8_10") (pintype "bidirectional"))
    )
    (net (code "15") (name "I2C_PW") (class "Default")
      (node (ref "C1") (pin "1") (pinfunction "1_1") (pintype "passive"))
      (node (ref "C2") (pin "1") (pinfunction "1_1") (pintype "passive"))
      (node (ref "R1_PINH") (pin "2") (pinfunction "2_2") (pintype "passive"))
      (node (ref "R2_PINH") (pin "2") (pinfunction "2_2") (pintype "passive"))
      (node (ref "SENSOR2") (pin "2") (pinfunction "CSB_2") (pintype "input"))
      (node (ref "SENSOR2") (pin "6") (pinfunction "VDDIO_6") (pintype "power_in"))
      (node (ref "SENSOR2") (pin "8") (pinfunction "VDD_8") (pintype "power_in"))
      (node (ref "U2") (pin "17") (pinfunction "IO19_17") (pintype "bidirectional"))
    )
    (net (code "16") (name "INT_RTC") (class "Default")
      (node (ref "R1_PINH1") (pin "1") (pinfunction "1_1") (pintype "passive"))
      (node (ref "TP15") (pin "TP") (pinfunction "TP_TP") (pintype "input"))
      (node (ref "U2") (pin "8") (pinfunction "IO0_8") (pintype "bidirectional"))
      (node (ref "U3") (pin "3") (pinfunction "SQW/~{INT}_3") (pintype "output"))
    )
    (net (code "17") (name "IO{slash}BOOT") (class "Default")
      (node (ref "BOOT_BUTTON") (pin "3") (pinfunction "3_3") (pintype "passive"))
      (node (ref "BOOT_BUTTON") (pin "4") (pinfunction "4_4") (pintype "passive"))
      (node (ref "C6") (pin "1") (pinfunction "1_1") (pintype "passive"))
      (node (ref "R_BOOT") (pin "1") (pinfunction "1_1") (pintype "passive"))
      (node (ref "U2") (pin "15") (pinfunction "IO9_15") (pintype "bidirectional"))
    )
    (net (code "18") (name "IO{slash}CHANGE") (class "Default")
      (node (ref "C10") (pin "1") (pinfunction "1_1") (pintype "passive"))
      (node (ref "CHANGE_BUTTON") (pin "3") (pinfunction "3_3") (pintype "passive"))
      (node (ref "CHANGE_BUTTON") (pin "4") (pinfunction "4_4") (pintype "passive"))
      (node (ref "R_CHANGE") (pin "1") (pinfunction "1_1") (pintype "passive"))
      (node (ref "U2") (pin "23") (pinfunction "IO15_23") (pintype "bidirectional"))
    )
    (net (code "19") (name "MISO") (class "Default")
      (node (ref "D12") (pin "2") (pinfunction "2_2") (pintype "passive"))
      (node (ref "J4") (pin "P7") (pinfunction "DAT0_P7") (pintype "bidirectional"))
      (node (ref "R8") (pin "1") (pinfunction "1_1") (pintype "passive"))
      (node (ref "TP6") (pin "TP") (pinfunction "TP_TP") (pintype "input"))
      (node (ref "U1") (pin "2") (pinfunction "DO(IO1)_2") (pintype "bidirectional"))
      (node (ref "U2") (pin "27") (pinfunction "IO2_27") (pintype "bidirectional"))
    )
    (net (code "20") (name "MOSI") (class "Default")
      (node (ref "D11") (pin "2") (pinfunction "2_2") (pintype "passive"))
      (node (ref "J1") (pin "14") (pinfunction "14_14") (pintype "bidirectional"))
      (node (ref "J4") (pin "P3") (pinfunction "CMD_P3") (pintype "bidirectional"))
      (node (ref "R7") (pin "1") (pinfunction "1_1") (pintype "passive"))
      (node (ref "TP7") (pin "TP") (pinfunction "TP_TP") (pintype "input"))
      (node (ref "U1") (pin "5") (pinfunction "DI(IO0)_5") (pintype "bidirectional"))
      (node (ref "U2") (pin "7") (pinfunction "IO7_7") (pintype "bidirectional"))
    )
    (net (code "21") (name "Net-(CHG_LED-PadC)") (class "Default")
      (node (ref "CHG_LED") (pin "C") (pinfunction "C_C") (pintype "passive"))
      (node (ref "R1_BAT") (pin "1") (pinfunction "1_1") (pintype "passive"))
    )
    (net (code "22") (name "Net-(D2-CATHODE)") (class "Default")
      (node (ref "C1_BAT1") (pin "1") (pinfunction "1_1") (pintype "passive"))
      (node (ref "D2") (pin "1") (pinfunction "CATHODE_1") (pintype "bidirectional"))
      (node (ref "IC4") (pin "1") (pinfunction "VIN_1") (pintype "bidirectional"))
      (node (ref "IC4") (pin "3") (pinfunction "CE_3") (pintype "bidirectional"))
      (node (ref "Q1") (pin "2") (pinfunction "S_2") (pintype "bidirectional"))
    )
    (net (code "23") (name "Net-(D3-A)") (class "Default")
      (node (ref "C4") (pin "1") (pinfunction "1_1") (pintype "passive"))
      (node (ref "D3") (pin "2") (pinfunction "A_2") (pintype "bidirectional"))
      (node (ref "D4") (pin "1") (pinfunction "K_1") (pintype "bidirectional"))
    )
    (net (code "24") (name "Net-(D7-CATHODE)") (class "Default")
      (node (ref "D7") (pin "1") (pinfunction "CATHODE_1") (pintype "bidirectional"))
      (node (ref "R_CAPACITOR") (pin "1") (pinfunction "1_1") (pintype "passive"))
    )
    (net (code "25") (name "Net-(EPD_C1-Pad2)") (class "Default")
      (node (ref "EPD_C1") (pin "2") (pinfunction "2_2") (pintype "passive"))
      (node (ref "J1") (pin "4") (pinfunction "4_4") (pintype "bidirectional"))
    )
    (net (code "26") (name "Net-(EPD_C2-Pad2)") (class "Default")
      (node (ref "EPD_C2") (pin "2") (pinfunction "2_2") (pintype "passive"))
      (node (ref "J1") (pin "5") (pinfunction "5_5") (pintype "bidirectional"))
    )
    (net (code "27") (name "Net-(EPD_C6-Pad2)") (class "Default")
      (node (ref "EPD_C6") (pin "2") (pinfunction "2_2") (pintype "passive"))
      (node (ref "J1") (pin "18") (pinfunction "18_18") (pintype "bidirectional"))
    )
    (net (code "28") (name "Net-(EPD_C7-Pad2)") (class "Default")
      (node (ref "EPD_C7") (pin "2") (pinfunction "2_2") (pintype "passive"))
      (node (ref "J1") (pin "19") (pinfunction "19_19") (pintype "bidirectional"))
    )
    (net (code "29") (name "Net-(EPD_C8-Pad2)") (class "Default")
      (node (ref "EPD_C8") (pin "2") (pinfunction "2_2") (pintype "passive"))
      (node (ref "J1") (pin "20") (pinfunction "20_20") (pintype "bidirectional"))
    )
    (net (code "30") (name "Net-(EPD_C10-Pad2)") (class "Default")
      (node (ref "EPD_C10") (pin "2") (pinfunction "2_2") (pintype "passive"))
      (node (ref "J1") (pin "22") (pinfunction "22_22") (pintype "bidirectional"))
    )
    (net (code "31") (name "Net-(EPD_C12-Pad2)") (class "Default")
      (node (ref "EPD_C12") (pin "2") (pinfunction "2_2") (pintype "passive"))
      (node (ref "J1") (pin "24") (pinfunction "24_24") (pintype "bidirectional"))
    )
    (net (code "32") (name "Net-(IC1-CT)") (class "Default")
      (node (ref "C_DELAY") (pin "1") (pinfunction "1_1") (pintype "passive"))
      (node (ref "IC1") (pin "5") (pinfunction "CT_5") (pintype "bidirectional"))
    )
    (net (code "33") (name "Net-(J2-PadA5)") (class "Default")
      (node (ref "J2") (pin "A5") (pinfunction "A5_A5") (pintype "bidirectional"))
      (node (ref "R2_USB1") (pin "2") (pinfunction "2_2") (pintype "passive"))
    )
    (net (code "34") (name "Net-(J2-PadB5)") (class "Default")
      (node (ref "J2") (pin "B5") (pinfunction "B5_B5") (pintype "bidirectional"))
      (node (ref "R2_USB") (pin "1") (pinfunction "1_1") (pintype "passive"))
    )
    (net (code "35") (name "Net-(MCP73831-PROG)") (class "Default")
      (node (ref "MCP73831") (pin "5") (pinfunction "PROG_5") (pintype "input"))
      (node (ref "R2_BAT") (pin "2") (pinfunction "2_2") (pintype "passive"))
    )
    (net (code "36") (name "Net-(MCP73831-STAT)") (class "Default")
      (node (ref "MCP73831") (pin "1") (pinfunction "STAT_1") (pintype "output"))
      (node (ref "R1_BAT") (pin "2") (pinfunction "2_2") (pintype "passive"))
    )
    (net (code "37") (name "PREVGH") (class "Default")
      (node (ref "D5") (pin "1") (pinfunction "K_1") (pintype "bidirectional"))
      (node (ref "EPD_C9") (pin "2") (pinfunction "2_2") (pintype "passive"))
      (node (ref "J1") (pin "21") (pinfunction "21_21") (pintype "bidirectional"))
    )
    (net (code "38") (name "PREVGL") (class "Default")
      (node (ref "D4") (pin "2") (pinfunction "A_2") (pintype "bidirectional"))
      (node (ref "EPD_C11") (pin "2") (pinfunction "2_2") (pintype "passive"))
      (node (ref "J1") (pin "23") (pinfunction "23_23") (pintype "bidirectional"))
    )
    (net (code "39") (name "RESE") (class "Default")
      (node (ref "J1") (pin "3") (pinfunction "3_3") (pintype "bidirectional"))
      (node (ref "Q3") (pin "2") (pinfunction "S_2") (pintype "bidirectional"))
      (node (ref "R3") (pin "2") (pinfunction "2_2") (pintype "passive"))
    )
    (net (code "40") (name "RESE'") (class "Default")
      (node (ref "R2") (pin "2") (pinfunction "2_2") (pintype "passive"))
      (node (ref "R3") (pin "1") (pinfunction "1_1") (pintype "passive"))
      (node (ref "SJ1") (pin "2") (pinfunction "2_2") (pintype "passive"))
    )
    (net (code "41") (name "RESET") (class "Default")
      (node (ref "C5") (pin "1") (pinfunction "1_1") (pintype "passive"))
      (node (ref "IC1") (pin "1") (pinfunction "VOUT_1") (pintype "bidirectional"))
      (node (ref "RESET_BUTTON") (pin "3") (pinfunction "3_3") (pintype "passive"))
      (node (ref "RESET_BUTTON") (pin "4") (pinfunction "4_4") (pintype "passive"))
      (node (ref "R_RESET") (pin "1") (pinfunction "1_1") (pintype "passive"))
      (node (ref "U2") (pin "3") (pinfunction "EN_3") (pintype "input"))
    )
    (net (code "42") (name "RTC_RST") (class "Default")
      (node (ref "U2") (pin "16") (pinfunction "IO18_16") (pintype "bidirectional"))
      (node (ref "U3") (pin "4") (pinfunction "~{RST}_4") (pintype "input"))
    )
    (net (code "43") (name "RX") (class "Default")
      (node (ref "TP2") (pin "TP") (pinfunction "TP_TP") (pintype "input"))
      (node (ref "U2") (pin "24") (pinfunction "RXD0/GPIO17_24") (pintype "bidirectional"))
    )
    (net (code "44") (name "SCK") (class "Default")
      (node (ref "D10") (pin "2") (pinfunction "2_2") (pintype "passive"))
      (node (ref "J1") (pin "13") (pinfunction "13_13") (pintype "bidirectional"))
      (node (ref "J4") (pin "P5") (pinfunction "CLK_P5") (pintype "bidirectional"))
      (node (ref "R6") (pin "1") (pinfunction "1_1") (pintype "passive"))
      (node (ref "TP8") (pin "TP") (pinfunction "TP_TP") (pintype "input"))
      (node (ref "U1") (pin "6") (pinfunction "CLK_6") (pintype "input"))
      (node (ref "U2") (pin "6") (pinfunction "IO6_6") (pintype "bidirectional"))
    )
    (net (code "45") (name "SCL") (class "Default")
      (node (ref "J3") (pin "4") (pinfunction "4_4") (pintype "passive"))
      (node (ref "R2_PINH") (pin "1") (pinfunction "1_1") (pintype "passive"))
      (node (ref "SENSOR2") (pin "4") (pinfunction "SCK_4") (pintype "input"))
      (node (ref "U2") (pin "20") (pinfunction "IO22_20") (pintype "bidirectional"))
      (node (ref "U3") (pin "16") (pinfunction "SCL_16") (pintype "input"))
      (node (ref "U4") (pin "7") (pinfunction "SCL_7") (pintype "input"))
    )
    (net (code "46") (name "SDA") (class "Default")
      (node (ref "J3") (pin "3") (pinfunction "3_3") (pintype "passive"))
      (node (ref "R1_PINH") (pin "1") (pinfunction "1_1") (pintype "passive"))
      (node (ref "SENSOR2") (pin "3") (pinfunction "SDI_3") (pintype "bidirectional"))
      (node (ref "U2") (pin "19") (pinfunction "IO21_19") (pintype "bidirectional"))
      (node (ref "U3") (pin "15") (pinfunction "SDA_15") (pintype "bidirectional"))
      (node (ref "U4") (pin "8") (pinfunction "SDA_8") (pintype "bidirectional"))
    )
    (net (code "47") (name "SRC") (class "Default")
      (node (ref "C4") (pin "2") (pinfunction "2_2") (pintype "passive"))
      (node (ref "D5") (pin "2") (pinfunction "A_2") (pintype "bidirectional"))
      (node (ref "L1") (pin "1") (pinfunction "1_1") (pintype "passive"))
      (node (ref "Q3") (pin "3") (pinfunction "D_3") (pintype "bidirectional"))
    )
    (net (code "48") (name "SS_SD") (class "Default")
      (node (ref "D8") (pin "2") (pinfunction "2_2") (pintype "passive"))
      (node (ref "J4") (pin "P2") (pinfunction "CD/DAT3_P2") (pintype "bidirectional"))
      (node (ref "R10") (pin "1") (pinfunction "1_1") (pintype "passive"))
      (node (ref "U2") (pin "4") (pinfunction "IO4_4") (pintype "bidirectional"))
    )
    (net (code "49") (name "TX") (class "Default")
      (node (ref "TP1") (pin "TP") (pinfunction "TP_TP") (pintype "input"))
      (node (ref "U2") (pin "25") (pinfunction "TXD0/GPIO16_25") (pintype "bidirectional"))
    )
    (net (code "50") (name "USB_D+") (class "Default")
      (node (ref "D1") (pin "1") (pinfunction "I/O1_1_1") (pintype "bidirectional"))
      (node (ref "U2") (pin "14") (pinfunction "IO13_14") (pintype "bidirectional"))
    )
    (net (code "51") (name "USB_D-") (class "Default")
      (node (ref "D1") (pin "3") (pinfunction "I/O2_1_3") (pintype "bidirectional"))
      (node (ref "U2") (pin "13") (pinfunction "IO12_13") (pintype "bidirectional"))
    )
    (net (code "52") (name "VBAT") (class "Default")
      (node (ref "C2_BAT") (pin "1") (pinfunction "1_1") (pintype "passive"))
      (node (ref "MCP73831") (pin "3") (pinfunction "VBAT_3") (pintype "power_in"))
      (node (ref "Q1") (pin "3") (pinfunction "D_3") (pintype "bidirectional"))
      (node (ref "TP3") (pin "TP") (pinfunction "TP_TP") (pintype "input"))
      (node (ref "U4") (pin "2") (pinfunction "CELL_2") (pintype "power_in"))
      (node (ref "U4") (pin "3") (pinfunction "VDD_3") (pintype "power_in"))
    )
    (net (code "53") (name "VBUS") (class "Default")
      (node (ref "C1_BAT") (pin "1") (pinfunction "1_1") (pintype "passive"))
      (node (ref "C4_USB") (pin "1") (pinfunction "1_1") (pintype "passive"))
      (node (ref "C5_USB") (pin "1") (pinfunction "1_1") (pintype "passive"))
      (node (ref "CHG_LED") (pin "A") (pinfunction "A_A") (pintype "passive"))
      (node (ref "D1") (pin "5") (pinfunction "VBUS_5") (pintype "bidirectional"))
      (node (ref "D2") (pin "2") (pinfunction "ANODE_2") (pintype "bidirectional"))
      (node (ref "MCP73831") (pin "4") (pinfunction "VIN_4") (pintype "power_in"))
      (node (ref "PFMF.050.1") (pin "2") (pinfunction "2_2") (pintype "passive"))
      (node (ref "Q1") (pin "1") (pinfunction "G_1") (pintype "bidirectional"))
      (node (ref "R1_PWRUSB") (pin "2") (pinfunction "2_2") (pintype "passive"))
      (node (ref "TP14") (pin "TP") (pinfunction "TP_TP") (pintype "input"))
    )
    (net (code "54") (name "VRTC") (class "Default")
      (node (ref "C10_SUPERCAP") (pin "2") (pinfunction "2_2") (pintype "passive"))
      (node (ref "C8") (pin "1") (pinfunction "1_1") (pintype "passive"))
      (node (ref "R_CAPACITOR") (pin "2") (pinfunction "2_2") (pintype "passive"))
      (node (ref "U3") (pin "14") (pinfunction "VBAT_14") (pintype "power_in"))
    )
    (net (code "55") (name "VUSB") (class "Default")
      (node (ref "J2") (pin "A4") (pinfunction "A4_A4") (pintype "bidirectional"))
      (node (ref "J2") (pin "A9") (pinfunction "A9_A9") (pintype "bidirectional"))
      (node (ref "J2") (pin "B4") (pinfunction "B4_B4") (pintype "bidirectional"))
      (node (ref "J2") (pin "B9") (pinfunction "B9_B9") (pintype "bidirectional"))
      (node (ref "PFMF.050.1") (pin "1") (pinfunction "1_1") (pintype "passive"))
    )
    (net (code "56") (name "unconnected-(IC1-NC-Pad4)") (class "Default")
      (node (ref "IC1") (pin "4") (pinfunction "NC_4") (pintype "no_connect"))
    )
    (net (code "57") (name "unconnected-(IC4-NC-Pad4)") (class "Default")
      (node (ref "IC4") (pin "4") (pinfunction "NC_4") (pintype "no_connect"))
    )
    (net (code "58") (name "unconnected-(J1-Pad1)") (class "Default")
      (node (ref "J1") (pin "1") (pinfunction "1_1") (pintype "bidirectional"))
    )
    (net (code "59") (name "unconnected-(J1-Pad6)") (class "Default")
      (node (ref "J1") (pin "6") (pinfunction "6_6") (pintype "bidirectional"))
    )
    (net (code "60") (name "unconnected-(J1-Pad7)") (class "Default")
      (node (ref "J1") (pin "7") (pinfunction "7_7") (pintype "bidirectional"))
    )
    (net (code "61") (name "unconnected-(J2-PadA8)") (class "Default")
      (node (ref "J2") (pin "A8") (pinfunction "A8_A8") (pintype "bidirectional"))
    )
    (net (code "62") (name "unconnected-(J2-PadB8)") (class "Default")
      (node (ref "J2") (pin "B8") (pinfunction "B8_B8") (pintype "bidirectional"))
    )
    (net (code "63") (name "unconnected-(J4-DAT1-PadP8)") (class "Default")
      (node (ref "J4") (pin "P8") (pinfunction "DAT1_P8") (pintype "bidirectional"))
    )
    (net (code "64") (name "unconnected-(J4-DAT2-PadP1)") (class "Default")
      (node (ref "J4") (pin "P1") (pinfunction "DAT2_P1") (pintype "bidirectional"))
    )
    (net (code "65") (name "unconnected-(J4-DETECTION_1-PadS1)") (class "Default")
      (node (ref "J4") (pin "S1") (pinfunction "DETECTION_1_S1") (pintype "bidirectional"))
    )
    (net (code "66") (name "unconnected-(J4-DETECTION_2-PadS2)") (class "Default")
      (node (ref "J4") (pin "S2") (pinfunction "DETECTION_2_S2") (pintype "bidirectional"))
    )
    (net (code "67") (name "unconnected-(U2-NC-Pad22)") (class "Default")
      (node (ref "U2") (pin "22") (pinfunction "NC_22") (pintype "no_connect"))
    )
    (net (code "68") (name "unconnected-(U4-~{ALERT}-Pad5)") (class "Default")
      (node (ref "U4") (pin "5") (pinfunction "~{ALERT}_5") (pintype "output"))
    )
  )
)
